# Relays.net
KiCad netlist of a schematic drawn in Altium Designer
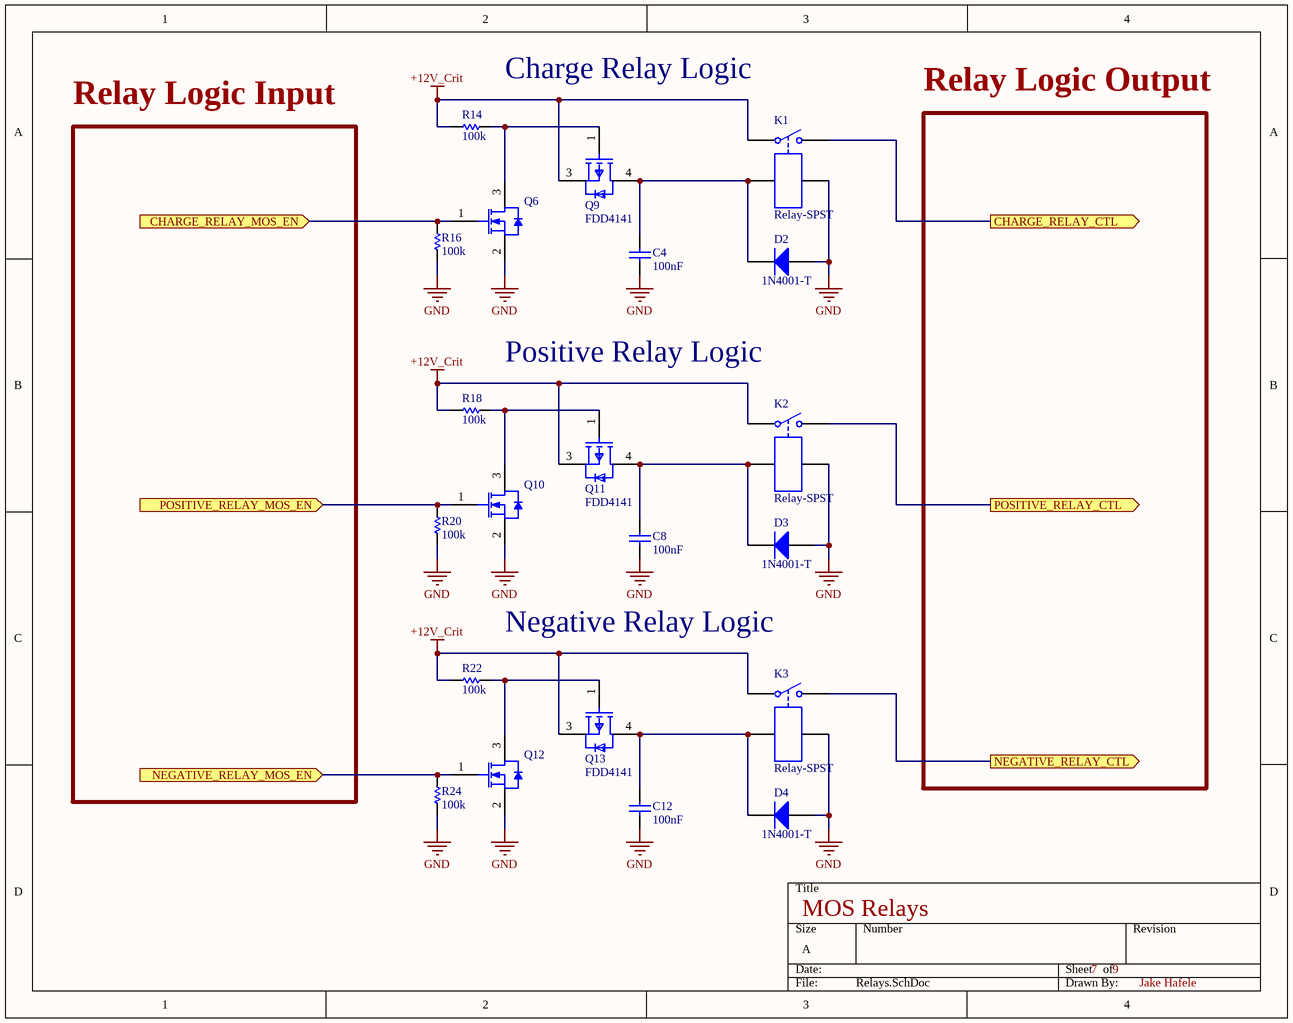
[diagram p0: Relays.SchDoc]

(export (version "E")
  (design (tool "Eeschema 10.0.6"))
  (components
    (comp (ref "C4")
      (value "100nF")
      (footprint "CAPC2113X120X50LL20T30")
      (description "TAJR104K035RNJ")
      (fields (field (name "MANUFACTURER") "AVX Interconnect / Elco"))
      (libsource (lib "Altium Content Vault") (part "CAP"))
    )
    (comp (ref "C8")
      (value "100nF")
      (footprint "CAPC2113X120X50LL20T30")
      (description "TAJR104K035RNJ")
      (fields (field (name "MANUFACTURER") "AVX Interconnect / Elco"))
      (libsource (lib "Altium Content Vault") (part "CAP"))
    )
    (comp (ref "C12")
      (value "100nF")
      (footprint "CAPC2113X120X50LL20T30")
      (description "TAJR104K035RNJ")
      (fields (field (name "MANUFACTURER") "AVX Interconnect / Elco"))
      (libsource (lib "Altium Content Vault") (part "CAP"))
    )
    (comp (ref "D2")
      (value "1N4001-T")
      (footprint "DIOD-DO-41-P-2_V")
      (description "1.0 A Rectifier, 15 pF, 50 V, -65 to 150 degC, 2-Pin DO-41 Plastic, RoHS, Tape and Reel")
      (fields (field (name "MANUFACTURER") "Diodes Inc"))
      (libsource (lib "Altium Content Vault") (part "DIOD-D-A1K2-2"))
    )
    (comp (ref "D3")
      (value "1N4001-T")
      (footprint "DIOD-DO-41-P-2_V")
      (description "1.0 A Rectifier, 15 pF, 50 V, -65 to 150 degC, 2-Pin DO-41 Plastic, RoHS, Tape and Reel")
      (fields (field (name "MANUFACTURER") "Diodes Inc"))
      (libsource (lib "Altium Content Vault") (part "DIOD-D-A1K2-2"))
    )
    (comp (ref "D4")
      (value "1N4001-T")
      (footprint "DIOD-DO-41-P-2_V")
      (description "1.0 A Rectifier, 15 pF, 50 V, -65 to 150 degC, 2-Pin DO-41 Plastic, RoHS, Tape and Reel")
      (fields (field (name "MANUFACTURER") "Diodes Inc"))
      (libsource (lib "Altium Content Vault") (part "DIOD-D-A1K2-2"))
    )
    (comp (ref "K1")
      (value "Relay-SPST")
      (footprint "Realy (G5CA)")
      (description "Single-Pole Single-Throw Relay")
      (fields (field (name "PUBLISHER") "Altium Limited"))
      (libsource (lib "BPS") (part "Relay-SPST"))
    )
    (comp (ref "K2")
      (value "Relay-SPST")
      (footprint "Realy (G5CA)")
      (description "Single-Pole Single-Throw Relay")
      (fields (field (name "PUBLISHER") "Altium Limited"))
      (libsource (lib "BPS") (part "Relay-SPST"))
    )
    (comp (ref "K3")
      (value "Relay-SPST")
      (footprint "Realy (G5CA)")
      (description "Single-Pole Single-Throw Relay")
      (fields (field (name "PUBLISHER") "Altium Limited"))
      (libsource (lib "BPS") (part "Relay-SPST"))
    )
    (comp (ref "Q6")
      (value "FDN337N")
      (footprint "FAIR-SSOT3L-3_V")
      (fields (field (name "MANUFACTURER") "Fairchild Semiconductor"))
      (libsource (lib "Altium Content Vault") (part "NEMOS-GSD-3"))
    )
    (comp (ref "Q9")
      (value "FDD4141")
      (footprint "FP-369AS-MFG")
      (description "MOSFET P-CH 40V 10.8A DPAK")
      (fields
        (field (name "OCTOPART") "https://octopart.com/fdd4141-on+semiconductor-84325802")
        (field (name "MANUFACTURER") "ON Semiconductor")
      )
      (libsource (lib "Altium Content Vault") (part "ec195c925100855187fe8c06440c3e1"))
    )
    (comp (ref "Q10")
      (value "FDN337N")
      (footprint "FAIR-SSOT3L-3_V")
      (fields (field (name "MANUFACTURER") "Fairchild Semiconductor"))
      (libsource (lib "Altium Content Vault") (part "NEMOS-GSD-3"))
    )
    (comp (ref "Q11")
      (value "FDD4141")
      (footprint "FP-369AS-MFG")
      (description "MOSFET P-CH 40V 10.8A DPAK")
      (fields
        (field (name "OCTOPART") "https://octopart.com/fdd4141-on+semiconductor-84325802")
        (field (name "MANUFACTURER") "ON Semiconductor")
      )
      (libsource (lib "Altium Content Vault") (part "ec195c925100855187fe8c06440c3e1"))
    )
    (comp (ref "Q12")
      (value "FDN337N")
      (footprint "FAIR-SSOT3L-3_V")
      (fields (field (name "MANUFACTURER") "Fairchild Semiconductor"))
      (libsource (lib "Altium Content Vault") (part "NEMOS-GSD-3"))
    )
    (comp (ref "Q13")
      (value "FDD4141")
      (footprint "FP-369AS-MFG")
      (description "MOSFET P-CH 40V 10.8A DPAK")
      (fields
        (field (name "OCTOPART") "https://octopart.com/fdd4141-on+semiconductor-84325802")
        (field (name "MANUFACTURER") "ON Semiconductor")
      )
      (libsource (lib "Altium Content Vault") (part "ec195c925100855187fe8c06440c3e1"))
    )
    (comp (ref "R14")
      (value "RES_100k_1%_0603")
      (footprint "R_0603")
      (fields
        (field (name "MANUFACTURER PART NUMBER") "RC0603FR-07100KL")
        (field (name "MANUFACTURER") "Yageo")
        (field (name "DIGIKEY PART NUMBER") "311-100KHRCT-ND")
        (field (name "SCHEMATICINFORMATION") "100k")
      )
      (libsource (lib "Resistors") (part "RES_100k_1%_0603"))
    )
    (comp (ref "R16")
      (value "RES_100k_1%_0603")
      (footprint "R_0603")
      (fields
        (field (name "MANUFACTURER PART NUMBER") "RC0603FR-07100KL")
        (field (name "MANUFACTURER") "Yageo")
        (field (name "DIGIKEY PART NUMBER") "311-100KHRCT-ND")
        (field (name "SCHEMATICINFORMATION") "100k")
      )
      (libsource (lib "Resistors") (part "RES_100k_1%_0603"))
    )
    (comp (ref "R18")
      (value "RES_100k_1%_0603")
      (footprint "R_0603")
      (fields
        (field (name "MANUFACTURER PART NUMBER") "RC0603FR-07100KL")
        (field (name "MANUFACTURER") "Yageo")
        (field (name "DIGIKEY PART NUMBER") "311-100KHRCT-ND")
        (field (name "SCHEMATICINFORMATION") "100k")
      )
      (libsource (lib "Resistors") (part "RES_100k_1%_0603"))
    )
    (comp (ref "R20")
      (value "RES_100k_1%_0603")
      (footprint "R_0603")
      (fields
        (field (name "MANUFACTURER PART NUMBER") "RC0603FR-07100KL")
        (field (name "MANUFACTURER") "Yageo")
        (field (name "DIGIKEY PART NUMBER") "311-100KHRCT-ND")
        (field (name "SCHEMATICINFORMATION") "100k")
      )
      (libsource (lib "Resistors") (part "RES_100k_1%_0603"))
    )
    (comp (ref "R22")
      (value "RES_100k_1%_0603")
      (footprint "R_0603")
      (fields
        (field (name "MANUFACTURER PART NUMBER") "RC0603FR-07100KL")
        (field (name "MANUFACTURER") "Yageo")
        (field (name "DIGIKEY PART NUMBER") "311-100KHRCT-ND")
        (field (name "SCHEMATICINFORMATION") "100k")
      )
      (libsource (lib "Resistors") (part "RES_100k_1%_0603"))
    )
    (comp (ref "R24")
      (value "RES_100k_1%_0603")
      (footprint "R_0603")
      (fields
        (field (name "MANUFACTURER PART NUMBER") "RC0603FR-07100KL")
        (field (name "MANUFACTURER") "Yageo")
        (field (name "DIGIKEY PART NUMBER") "311-100KHRCT-ND")
        (field (name "SCHEMATICINFORMATION") "100k")
      )
      (libsource (lib "Resistors") (part "RES_100k_1%_0603"))
    )
  )
  (nets
    (net (code "1") (name "+12V_Crit") (class "Default")
      (node (ref "K1") (pin "4") (pinfunction "4_4") (pintype "passive"))
      (node (ref "K2") (pin "4") (pinfunction "4_4") (pintype "passive"))
      (node (ref "K3") (pin "4") (pinfunction "4_4") (pintype "passive"))
      (node (ref "Q11") (pin "3") (pinfunction "S_3") (pintype "passive"))
      (node (ref "Q13") (pin "3") (pinfunction "S_3") (pintype "passive"))
      (node (ref "Q9") (pin "3") (pinfunction "S_3") (pintype "passive"))
      (node (ref "R14") (pin "1") (pinfunction "1_1") (pintype "passive"))
      (node (ref "R18") (pin "1") (pinfunction "1_1") (pintype "passive"))
      (node (ref "R22") (pin "1") (pinfunction "1_1") (pintype "passive"))
    )
    (net (code "2") (name "/CHARGE_RELAY_CTL") (class "Default")
      (node (ref "K1") (pin "3") (pinfunction "3_3") (pintype "passive"))
    )
    (net (code "3") (name "/CHARGE_RELAY_MOS_EN") (class "Default")
      (node (ref "Q6") (pin "1") (pinfunction "G_1") (pintype "passive"))
      (node (ref "R16") (pin "2") (pinfunction "2_2") (pintype "passive"))
    )
    (net (code "4") (name "/NEGATIVE_RELAY_CTL") (class "Default")
      (node (ref "K3") (pin "3") (pinfunction "3_3") (pintype "passive"))
    )
    (net (code "5") (name "/NEGATIVE_RELAY_MOS_EN") (class "Default")
      (node (ref "Q12") (pin "1") (pinfunction "G_1") (pintype "passive"))
      (node (ref "R24") (pin "2") (pinfunction "2_2") (pintype "passive"))
    )
    (net (code "6") (name "/POSITIVE_RELAY_CTL") (class "Default")
      (node (ref "K2") (pin "3") (pinfunction "3_3") (pintype "passive"))
    )
    (net (code "7") (name "/POSITIVE_RELAY_MOS_EN") (class "Default")
      (node (ref "Q10") (pin "1") (pinfunction "G_1") (pintype "passive"))
      (node (ref "R20") (pin "2") (pinfunction "2_2") (pintype "passive"))
    )
    (net (code "8") (name "GND") (class "Default")
      (node (ref "C12") (pin "2") (pinfunction "2_2") (pintype "passive"))
      (node (ref "C4") (pin "2") (pinfunction "2_2") (pintype "passive"))
      (node (ref "C8") (pin "2") (pinfunction "2_2") (pintype "passive"))
      (node (ref "D2") (pin "1") (pinfunction "A_1") (pintype "passive"))
      (node (ref "D3") (pin "1") (pinfunction "A_1") (pintype "passive"))
      (node (ref "D4") (pin "1") (pinfunction "A_1") (pintype "passive"))
      (node (ref "K1") (pin "2") (pinfunction "2_2") (pintype "passive"))
      (node (ref "K2") (pin "2") (pinfunction "2_2") (pintype "passive"))
      (node (ref "K3") (pin "2") (pinfunction "2_2") (pintype "passive"))
      (node (ref "Q10") (pin "2") (pinfunction "S_2") (pintype "passive"))
      (node (ref "Q12") (pin "2") (pinfunction "S_2") (pintype "passive"))
      (node (ref "Q6") (pin "2") (pinfunction "S_2") (pintype "passive"))
      (node (ref "R16") (pin "1") (pinfunction "1_1") (pintype "passive"))
      (node (ref "R20") (pin "1") (pinfunction "1_1") (pintype "passive"))
      (node (ref "R24") (pin "1") (pinfunction "1_1") (pintype "passive"))
    )
    (net (code "9") (name "Net-(D2-K)") (class "Default")
      (node (ref "C4") (pin "1") (pinfunction "1_1") (pintype "passive"))
      (node (ref "D2") (pin "2") (pinfunction "K_2") (pintype "passive"))
      (node (ref "K1") (pin "1") (pinfunction "1_1") (pintype "passive"))
      (node (ref "Q9") (pin "4") (pinfunction "D_4") (pintype "passive"))
    )
    (net (code "10") (name "Net-(D3-K)") (class "Default")
      (node (ref "C8") (pin "1") (pinfunction "1_1") (pintype "passive"))
      (node (ref "D3") (pin "2") (pinfunction "K_2") (pintype "passive"))
      (node (ref "K2") (pin "1") (pinfunction "1_1") (pintype "passive"))
      (node (ref "Q11") (pin "4") (pinfunction "D_4") (pintype "passive"))
    )
    (net (code "11") (name "Net-(D4-K)") (class "Default")
      (node (ref "C12") (pin "1") (pinfunction "1_1") (pintype "passive"))
      (node (ref "D4") (pin "2") (pinfunction "K_2") (pintype "passive"))
      (node (ref "K3") (pin "1") (pinfunction "1_1") (pintype "passive"))
      (node (ref "Q13") (pin "4") (pinfunction "D_4") (pintype "passive"))
    )
    (net (code "12") (name "Net-(Q6-D)") (class "Default")
      (node (ref "Q6") (pin "3") (pinfunction "D_3") (pintype "passive"))
      (node (ref "Q9") (pin "1") (pinfunction "G_1") (pintype "passive"))
      (node (ref "R14") (pin "2") (pinfunction "2_2") (pintype "passive"))
    )
    (net (code "13") (name "Net-(Q10-D)") (class "Default")
      (node (ref "Q10") (pin "3") (pinfunction "D_3") (pintype "passive"))
      (node (ref "Q11") (pin "1") (pinfunction "G_1") (pintype "passive"))
      (node (ref "R18") (pin "2") (pinfunction "2_2") (pintype "passive"))
    )
    (net (code "14") (name "Net-(Q12-D)") (class "Default")
      (node (ref "Q12") (pin "3") (pinfunction "D_3") (pintype "passive"))
      (node (ref "Q13") (pin "1") (pinfunction "G_1") (pintype "passive"))
      (node (ref "R22") (pin "2") (pinfunction "2_2") (pintype "passive"))
    )
  )
)
